# TC2030-NL_TagConnect_6-pin.net
KiCad netlist of a schematic drawn in Altium Designer
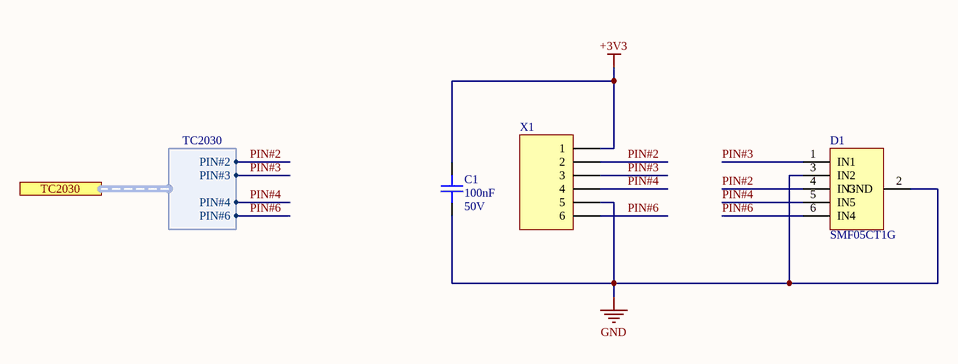
[diagram p0: TC2030-NL_TagConnect_6-pin.SchDoc]

(export (version "E")
  (design (tool "Eeschema 10.0.6"))
  (components
    (comp (ref "C1")
      (value "CAP CER 0.1UF 50V X7R 0402")
      (footprint "C0402")
      (description "0.1µF ±10% 50V Ceramic Capacitor X7R 0402 (1005 Metric)")
      (fields
        (field (name "MANUFACTURER") "TDK")
        (field (name "MANUFACTURER PART NUMBER") "CGA2B3X7R1H104K050BB")
        (field (name "CAPACITANCE") "100nF")
        (field (name "VOLTAGE") "50V")
      )
      (libsource (lib "capacitors_smd") (part "CAP CER 0.1UF 50V X7R 0402"))
    )
    (comp (ref "D1")
      (value "SMF05CT1G")
      (footprint "SOT363_SOP65P210X265-6N")
      (description "12.5V Clamp 8A (8/20µs) Ipp Tvs Diode Surface Mount SC-88/SC70-6/SOT-363")
      (fields (field (name "MANUFACTURER") "ON Semiconductor"))
      (libsource (lib "diodes_tvs") (part "TVS DIODE 5V 12.5V 5CH SC88"))
    )
    (comp (ref "X1")
      (value "~")
      (footprint "TC2030-IDC-NL")
      (description "Tag-Connect TC2030-MCP-NL (3x2 pins No Legs)")
      (fields
        (field (name "MANUFACTURER") "Tag-Connect LLC")
        (field (name "MANUFACTURER PART NUMBER") "TC2030-IDC-NL")
      )
      (libsource (lib "EvansWerks") (part "TC2030-IDC-NL"))
    )
  )
  (nets
    (net (code "2") (name "+3V3") (class "Default")
      (node (ref "C1") (pin "2") (pinfunction "2_2") (pintype "passive"))
      (node (ref "X1") (pin "1") (pinfunction "1_1") (pintype "passive"))
    )
    (net (code "3") (name "/PIN#2") (class "Default")
      (node (ref "D1") (pin "4") (pinfunction "IN3_4") (pintype "passive"))
      (node (ref "X1") (pin "2") (pinfunction "2_2") (pintype "passive"))
    )
    (net (code "4") (name "/PIN#3") (class "Default")
      (node (ref "D1") (pin "1") (pinfunction "IN1_1") (pintype "passive"))
      (node (ref "X1") (pin "3") (pinfunction "3_3") (pintype "passive"))
    )
    (net (code "5") (name "/PIN#4") (class "Default")
      (node (ref "D1") (pin "5") (pinfunction "IN5_5") (pintype "passive"))
      (node (ref "X1") (pin "4") (pinfunction "4_4") (pintype "passive"))
    )
    (net (code "6") (name "/PIN#6") (class "Default")
      (node (ref "D1") (pin "6") (pinfunction "IN4_6") (pintype "passive"))
      (node (ref "X1") (pin "6") (pinfunction "6_6") (pintype "passive"))
    )
    (net (code "8") (name "GND") (class "Default")
      (node (ref "C1") (pin "1") (pinfunction "1_1") (pintype "passive"))
      (node (ref "D1") (pin "2") (pinfunction "GND_2") (pintype "power_in"))
      (node (ref "D1") (pin "3") (pinfunction "IN2_3") (pintype "passive"))
      (node (ref "X1") (pin "5") (pinfunction "5_5") (pintype "passive"))
    )
  )
)
